# DCoffset.net
KiCad netlist of a schematic drawn in Altium Designer
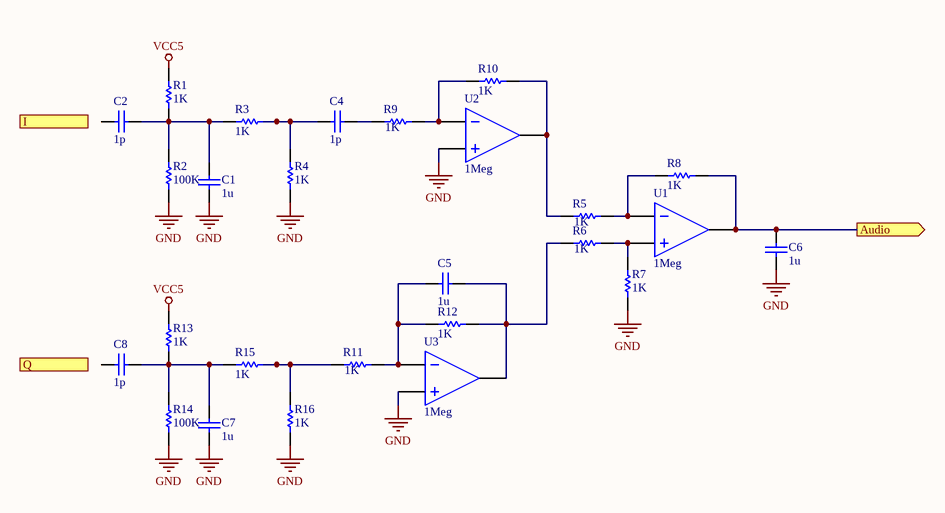
[diagram p0: DCoffset.SchDoc]

(export (version "E")
  (design (tool "Eeschema 10.0.6"))
  (components
    (comp (ref "C1")
      (value "1u")
      (description "Capacitor")
      (libsource (lib "Simulation Generic Components") (part "Capacitor"))
    )
    (comp (ref "C2")
      (value "1p")
      (description "Capacitor")
      (libsource (lib "Simulation Generic Components") (part "Capacitor"))
    )
    (comp (ref "C4")
      (value "1p")
      (description "Capacitor")
      (libsource (lib "Simulation Generic Components") (part "Capacitor"))
    )
    (comp (ref "C5")
      (value "1u")
      (description "Capacitor")
      (libsource (lib "Simulation Generic Components") (part "Capacitor"))
    )
    (comp (ref "C6")
      (value "1u")
      (description "Capacitor")
      (libsource (lib "Simulation Generic Components") (part "Capacitor"))
    )
    (comp (ref "C7")
      (value "1u")
      (description "Capacitor")
      (libsource (lib "Simulation Generic Components") (part "Capacitor"))
    )
    (comp (ref "C8")
      (value "1p")
      (description "Capacitor")
      (libsource (lib "Simulation Generic Components") (part "Capacitor"))
    )
    (comp (ref "R1")
      (value "1K")
      (description "Resistor")
      (libsource (lib "Simulation Generic Components") (part "Resistor"))
    )
    (comp (ref "R2")
      (value "100K")
      (description "Resistor")
      (libsource (lib "Simulation Generic Components") (part "Resistor"))
    )
    (comp (ref "R3")
      (value "1K")
      (description "Resistor")
      (libsource (lib "Simulation Generic Components") (part "Resistor"))
    )
    (comp (ref "R4")
      (value "1K")
      (description "Resistor")
      (libsource (lib "Simulation Generic Components") (part "Resistor"))
    )
    (comp (ref "R5")
      (value "1K")
      (description "Resistor")
      (libsource (lib "Simulation Generic Components") (part "Resistor"))
    )
    (comp (ref "R6")
      (value "1K")
      (description "Resistor")
      (libsource (lib "Simulation Generic Components") (part "Resistor"))
    )
    (comp (ref "R7")
      (value "1K")
      (description "Resistor")
      (libsource (lib "Simulation Generic Components") (part "Resistor"))
    )
    (comp (ref "R8")
      (value "1K")
      (description "Resistor")
      (libsource (lib "Simulation Generic Components") (part "Resistor"))
    )
    (comp (ref "R9")
      (value "1K")
      (description "Resistor")
      (libsource (lib "Simulation Generic Components") (part "Resistor"))
    )
    (comp (ref "R10")
      (value "1K")
      (description "Resistor")
      (libsource (lib "Simulation Generic Components") (part "Resistor"))
    )
    (comp (ref "R11")
      (value "1K")
      (description "Resistor")
      (libsource (lib "Simulation Generic Components") (part "Resistor"))
    )
    (comp (ref "R12")
      (value "1K")
      (description "Resistor")
      (libsource (lib "Simulation Generic Components") (part "Resistor"))
    )
    (comp (ref "R13")
      (value "1K")
      (description "Resistor")
      (libsource (lib "Simulation Generic Components") (part "Resistor"))
    )
    (comp (ref "R14")
      (value "100K")
      (description "Resistor")
      (libsource (lib "Simulation Generic Components") (part "Resistor"))
    )
    (comp (ref "R15")
      (value "1K")
      (description "Resistor")
      (libsource (lib "Simulation Generic Components") (part "Resistor"))
    )
    (comp (ref "R16")
      (value "1K")
      (description "Resistor")
      (libsource (lib "Simulation Generic Components") (part "Resistor"))
    )
    (comp (ref "U1")
      (value "Ideal Operational Amplifier")
      (fields (field (name "GAIN") "1Meg"))
      (libsource (lib "Simulation Generic Components") (part "OpAmp"))
    )
    (comp (ref "U2")
      (value "Ideal Operational Amplifier")
      (fields (field (name "GAIN") "1Meg"))
      (libsource (lib "Simulation Generic Components") (part "OpAmp"))
    )
    (comp (ref "U3")
      (value "Ideal Operational Amplifier")
      (fields (field (name "GAIN") "1Meg"))
      (libsource (lib "Simulation Generic Components") (part "OpAmp"))
    )
  )
  (nets
    (net (code "1") (name "/Audio") (class "Default")
      (node (ref "C6") (pin "2") (pinfunction "2_2") (pintype "passive"))
      (node (ref "R8") (pin "1") (pinfunction "1_1") (pintype "passive"))
      (node (ref "U1") (pin "3") (pinfunction "OUT_3") (pintype "passive"))
    )
    (net (code "4") (name "GND") (class "Default")
      (node (ref "C1") (pin "1") (pinfunction "1_1") (pintype "passive"))
      (node (ref "C6") (pin "1") (pinfunction "1_1") (pintype "passive"))
      (node (ref "C7") (pin "1") (pinfunction "1_1") (pintype "passive"))
      (node (ref "R14") (pin "1") (pinfunction "1_1") (pintype "passive"))
      (node (ref "R16") (pin "2") (pinfunction "2_2") (pintype "passive"))
      (node (ref "R2") (pin "1") (pinfunction "1_1") (pintype "passive"))
      (node (ref "R4") (pin "2") (pinfunction "2_2") (pintype "passive"))
      (node (ref "R7") (pin "1") (pinfunction "1_1") (pintype "passive"))
      (node (ref "U2") (pin "2") (pinfunction "IN+_2") (pintype "passive"))
      (node (ref "U3") (pin "2") (pinfunction "IN+_2") (pintype "passive"))
    )
    (net (code "5") (name "Net-(C1-Pad2)") (class "Default")
      (node (ref "C1") (pin "2") (pinfunction "2_2") (pintype "passive"))
      (node (ref "C2") (pin "2") (pinfunction "2_2") (pintype "passive"))
      (node (ref "R1") (pin "1") (pinfunction "1_1") (pintype "passive"))
      (node (ref "R2") (pin "2") (pinfunction "2_2") (pintype "passive"))
      (node (ref "R3") (pin "2") (pinfunction "2_2") (pintype "passive"))
    )
    (net (code "6") (name "Net-(C4-Pad1)") (class "Default")
      (node (ref "C4") (pin "1") (pinfunction "1_1") (pintype "passive"))
      (node (ref "R3") (pin "1") (pinfunction "1_1") (pintype "passive"))
      (node (ref "R4") (pin "1") (pinfunction "1_1") (pintype "passive"))
    )
    (net (code "7") (name "Net-(C4-Pad2)") (class "Default")
      (node (ref "C4") (pin "2") (pinfunction "2_2") (pintype "passive"))
      (node (ref "R9") (pin "2") (pinfunction "2_2") (pintype "passive"))
    )
    (net (code "8") (name "Net-(C7-Pad2)") (class "Default")
      (node (ref "C7") (pin "2") (pinfunction "2_2") (pintype "passive"))
      (node (ref "C8") (pin "2") (pinfunction "2_2") (pintype "passive"))
      (node (ref "R13") (pin "1") (pinfunction "1_1") (pintype "passive"))
      (node (ref "R14") (pin "2") (pinfunction "2_2") (pintype "passive"))
      (node (ref "R15") (pin "2") (pinfunction "2_2") (pintype "passive"))
    )
    (net (code "9") (name "Net-(R11-Pad2)") (class "Default")
      (node (ref "R11") (pin "2") (pinfunction "2_2") (pintype "passive"))
      (node (ref "R15") (pin "1") (pinfunction "1_1") (pintype "passive"))
      (node (ref "R16") (pin "1") (pinfunction "1_1") (pintype "passive"))
    )
    (net (code "10") (name "Net-(U1-IN+)") (class "Default")
      (node (ref "R6") (pin "1") (pinfunction "1_1") (pintype "passive"))
      (node (ref "R7") (pin "2") (pinfunction "2_2") (pintype "passive"))
      (node (ref "U1") (pin "2") (pinfunction "IN+_2") (pintype "passive"))
    )
    (net (code "11") (name "Net-(U1-IN-)") (class "Default")
      (node (ref "R5") (pin "1") (pinfunction "1_1") (pintype "passive"))
      (node (ref "R8") (pin "2") (pinfunction "2_2") (pintype "passive"))
      (node (ref "U1") (pin "1") (pinfunction "IN-_1") (pintype "passive"))
    )
    (net (code "12") (name "Net-(U2-IN-)") (class "Default")
      (node (ref "R10") (pin "2") (pinfunction "2_2") (pintype "passive"))
      (node (ref "R9") (pin "1") (pinfunction "1_1") (pintype "passive"))
      (node (ref "U2") (pin "1") (pinfunction "IN-_1") (pintype "passive"))
    )
    (net (code "13") (name "Net-(U2-OUT)") (class "Default")
      (node (ref "R10") (pin "1") (pinfunction "1_1") (pintype "passive"))
      (node (ref "R5") (pin "2") (pinfunction "2_2") (pintype "passive"))
      (node (ref "U2") (pin "3") (pinfunction "OUT_3") (pintype "passive"))
    )
    (net (code "14") (name "Net-(U3-IN-)") (class "Default")
      (node (ref "C5") (pin "2") (pinfunction "2_2") (pintype "passive"))
      (node (ref "R11") (pin "1") (pinfunction "1_1") (pintype "passive"))
      (node (ref "R12") (pin "2") (pinfunction "2_2") (pintype "passive"))
      (node (ref "U3") (pin "1") (pinfunction "IN-_1") (pintype "passive"))
    )
    (net (code "15") (name "Net-(U3-OUT)") (class "Default")
      (node (ref "C5") (pin "1") (pinfunction "1_1") (pintype "passive"))
      (node (ref "R12") (pin "1") (pinfunction "1_1") (pintype "passive"))
      (node (ref "R6") (pin "2") (pinfunction "2_2") (pintype "passive"))
      (node (ref "U3") (pin "3") (pinfunction "OUT_3") (pintype "passive"))
    )
    (net (code "16") (name "VCC5") (class "Default")
      (node (ref "R1") (pin "2") (pinfunction "2_2") (pintype "passive"))
      (node (ref "R13") (pin "2") (pinfunction "2_2") (pintype "passive"))
    )
    (net (code "17") (name "unconnected-(C2-Pad1)") (class "Default")
      (node (ref "C2") (pin "1") (pinfunction "1_1") (pintype "passive"))
    )
    (net (code "18") (name "unconnected-(C8-Pad1)") (class "Default")
      (node (ref "C8") (pin "1") (pinfunction "1_1") (pintype "passive"))
    )
  )
)
